# Channel_A.net
KiCad netlist of a schematic drawn in Altium Designer
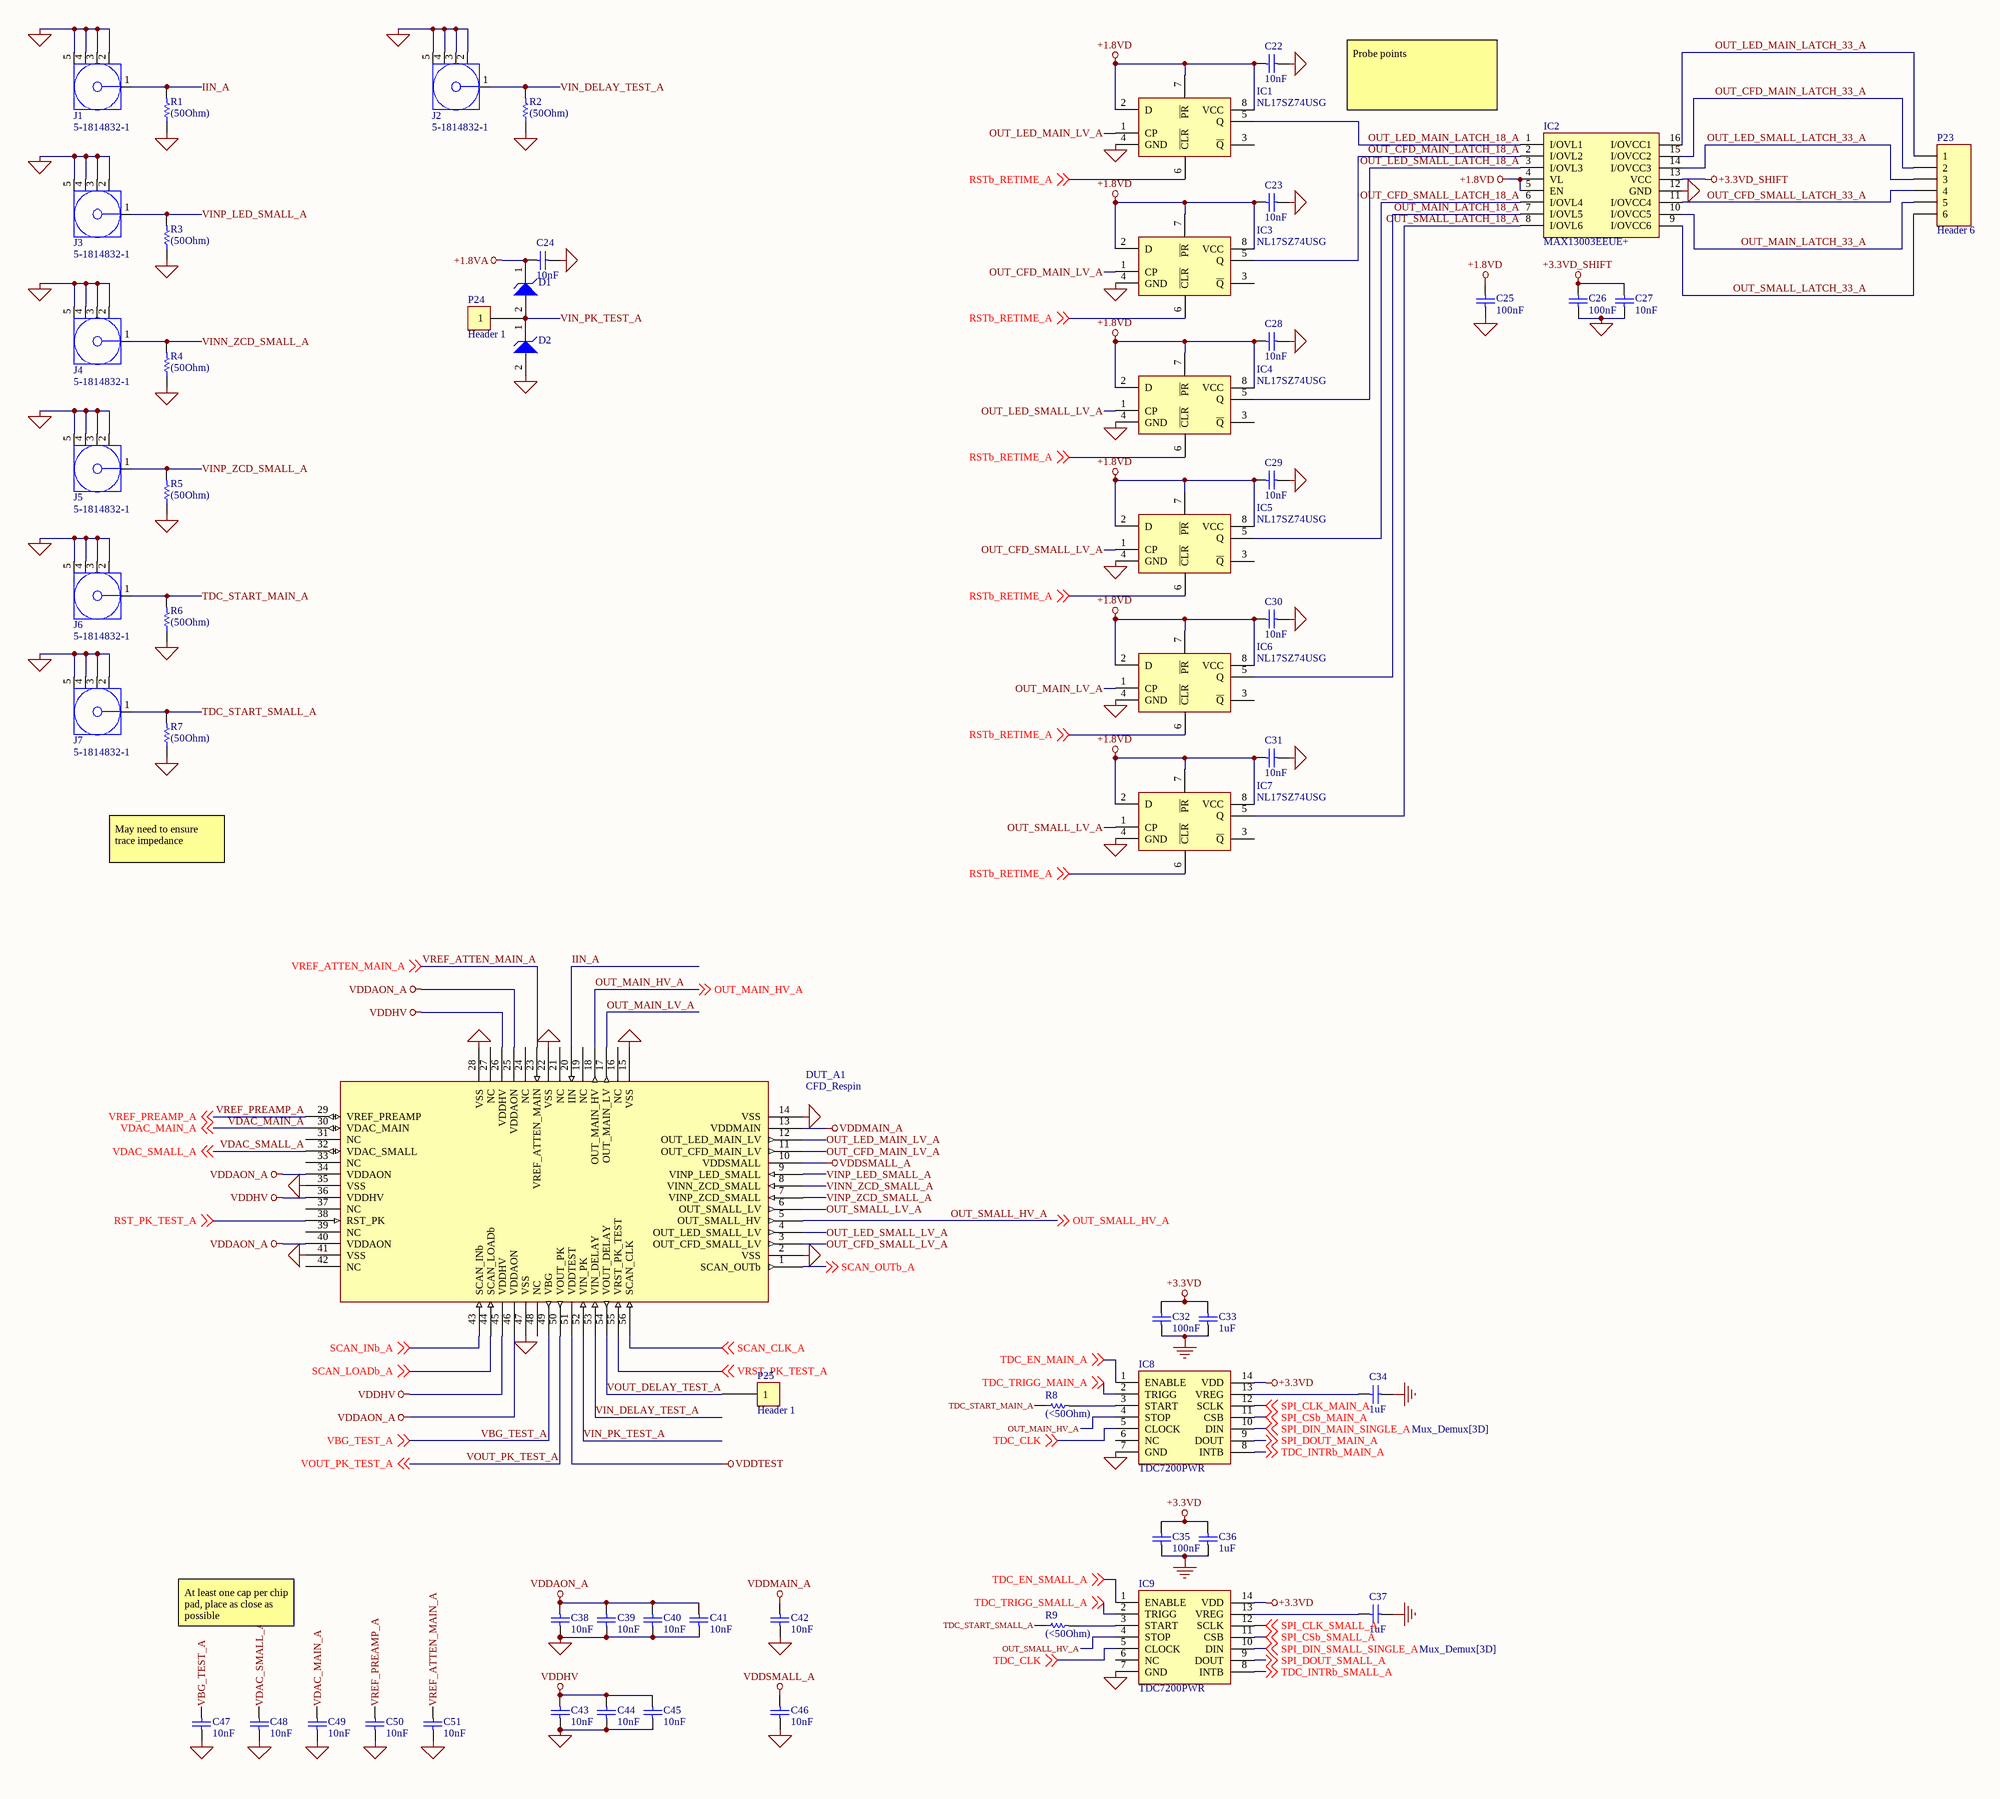
[diagram p0: Channel_A.SchDoc]

(export (version "E")
  (design (tool "Eeschema 10.0.6"))
  (components
    (comp (ref "C22")
      (value "10nF")
      (footprint "CAPC1608X90X35ML10T15")
      (description "0603")
      (fields (field (name "MANUFACTURER") "Murata"))
      (libsource (lib "Altium Content Vault") (part "CAP-NP-2"))
    )
    (comp (ref "C23")
      (value "10nF")
      (footprint "CAPC1608X90X35ML10T15")
      (description "0603")
      (fields (field (name "MANUFACTURER") "Murata"))
      (libsource (lib "Altium Content Vault") (part "CAP-NP-2"))
    )
    (comp (ref "C24")
      (value "10nF")
      (footprint "CAPC1608X90X35ML10T15")
      (description "0603")
      (fields (field (name "MANUFACTURER") "Murata"))
      (libsource (lib "Altium Content Vault") (part "CAP-NP-2"))
    )
    (comp (ref "C25")
      (value "100nF")
      (footprint "CAPC1608X90X35ML10T15")
      (description "0603")
      (fields (field (name "MANUFACTURER") "Murata"))
      (libsource (lib "Altium Content Vault") (part "CAP-NP-2"))
    )
    (comp (ref "C26")
      (value "100nF")
      (footprint "CAPC1608X90X35ML10T15")
      (description "0603")
      (fields (field (name "MANUFACTURER") "Murata"))
      (libsource (lib "Altium Content Vault") (part "CAP-NP-2"))
    )
    (comp (ref "C27")
      (value "10nF")
      (footprint "CAPC1608X90X35ML10T15")
      (description "0603")
      (fields (field (name "MANUFACTURER") "Murata"))
      (libsource (lib "Altium Content Vault") (part "CAP-NP-2"))
    )
    (comp (ref "C28")
      (value "10nF")
      (footprint "CAPC1608X90X35ML10T15")
      (description "0603")
      (fields (field (name "MANUFACTURER") "Murata"))
      (libsource (lib "Altium Content Vault") (part "CAP-NP-2"))
    )
    (comp (ref "C29")
      (value "10nF")
      (footprint "CAPC1608X90X35ML10T15")
      (description "0603")
      (fields (field (name "MANUFACTURER") "Murata"))
      (libsource (lib "Altium Content Vault") (part "CAP-NP-2"))
    )
    (comp (ref "C30")
      (value "10nF")
      (footprint "CAPC1608X90X35ML10T15")
      (description "0603")
      (fields (field (name "MANUFACTURER") "Murata"))
      (libsource (lib "Altium Content Vault") (part "CAP-NP-2"))
    )
    (comp (ref "C31")
      (value "10nF")
      (footprint "CAPC1608X90X35ML10T15")
      (description "0603")
      (fields (field (name "MANUFACTURER") "Murata"))
      (libsource (lib "Altium Content Vault") (part "CAP-NP-2"))
    )
    (comp (ref "C32")
      (value "100nF")
      (footprint "CAPC1608X90X35ML10T15")
      (description "0603")
      (fields (field (name "MANUFACTURER") "Murata"))
      (libsource (lib "Altium Content Vault") (part "CAP-NP-2"))
    )
    (comp (ref "C33")
      (value "1uF")
      (footprint "CAPC1608X90X35ML10T15")
      (description "0603")
      (fields (field (name "MANUFACTURER") "Murata"))
      (libsource (lib "Altium Content Vault") (part "CAP-NP-2"))
    )
    (comp (ref "C34")
      (value "1uF")
      (footprint "CAPC1608X90X35ML10T15")
      (description "0603")
      (fields (field (name "MANUFACTURER") "Murata"))
      (libsource (lib "Altium Content Vault") (part "CAP-NP-2"))
    )
    (comp (ref "C35")
      (value "100nF")
      (footprint "CAPC1608X90X35ML10T15")
      (description "0603")
      (fields (field (name "MANUFACTURER") "Murata"))
      (libsource (lib "Altium Content Vault") (part "CAP-NP-2"))
    )
    (comp (ref "C36")
      (value "1uF")
      (footprint "CAPC1608X90X35ML10T15")
      (description "0603")
      (fields (field (name "MANUFACTURER") "Murata"))
      (libsource (lib "Altium Content Vault") (part "CAP-NP-2"))
    )
    (comp (ref "C37")
      (value "1uF")
      (footprint "CAPC1608X90X35ML10T15")
      (description "0603")
      (fields (field (name "MANUFACTURER") "Murata"))
      (libsource (lib "Altium Content Vault") (part "CAP-NP-2"))
    )
    (comp (ref "C38")
      (value "10nF")
      (footprint "CAPC1608X90X35ML10T15")
      (description "0603")
      (fields (field (name "MANUFACTURER") "Murata"))
      (libsource (lib "Altium Content Vault") (part "CAP-NP-2"))
    )
    (comp (ref "C39")
      (value "10nF")
      (footprint "CAPC1608X90X35ML10T15")
      (description "0603")
      (fields (field (name "MANUFACTURER") "Murata"))
      (libsource (lib "Altium Content Vault") (part "CAP-NP-2"))
    )
    (comp (ref "C40")
      (value "10nF")
      (footprint "CAPC1608X90X35ML10T15")
      (description "0603")
      (fields (field (name "MANUFACTURER") "Murata"))
      (libsource (lib "Altium Content Vault") (part "CAP-NP-2"))
    )
    (comp (ref "C41")
      (value "10nF")
      (footprint "CAPC1608X90X35ML10T15")
      (description "0603")
      (fields (field (name "MANUFACTURER") "Murata"))
      (libsource (lib "Altium Content Vault") (part "CAP-NP-2"))
    )
    (comp (ref "C42")
      (value "10nF")
      (footprint "CAPC1608X90X35ML10T15")
      (description "0603")
      (fields (field (name "MANUFACTURER") "Murata"))
      (libsource (lib "Altium Content Vault") (part "CAP-NP-2"))
    )
    (comp (ref "C43")
      (value "10nF")
      (footprint "CAPC1608X90X35ML10T15")
      (description "0603")
      (fields (field (name "MANUFACTURER") "Murata"))
      (libsource (lib "Altium Content Vault") (part "CAP-NP-2"))
    )
    (comp (ref "C44")
      (value "10nF")
      (footprint "CAPC1608X90X35ML10T15")
      (description "0603")
      (fields (field (name "MANUFACTURER") "Murata"))
      (libsource (lib "Altium Content Vault") (part "CAP-NP-2"))
    )
    (comp (ref "C45")
      (value "10nF")
      (footprint "CAPC1608X90X35ML10T15")
      (description "0603")
      (fields (field (name "MANUFACTURER") "Murata"))
      (libsource (lib "Altium Content Vault") (part "CAP-NP-2"))
    )
    (comp (ref "C46")
      (value "10nF")
      (footprint "CAPC1608X90X35ML10T15")
      (description "0603")
      (fields (field (name "MANUFACTURER") "Murata"))
      (libsource (lib "Altium Content Vault") (part "CAP-NP-2"))
    )
    (comp (ref "C47")
      (value "10nF")
      (footprint "CAPC1608X90X35ML10T15")
      (description "0603")
      (fields (field (name "MANUFACTURER") "Murata"))
      (libsource (lib "Altium Content Vault") (part "CAP-NP-2"))
    )
    (comp (ref "C48")
      (value "10nF")
      (footprint "CAPC1608X90X35ML10T15")
      (description "0603")
      (fields (field (name "MANUFACTURER") "Murata"))
      (libsource (lib "Altium Content Vault") (part "CAP-NP-2"))
    )
    (comp (ref "C49")
      (value "10nF")
      (footprint "CAPC1608X90X35ML10T15")
      (description "0603")
      (fields (field (name "MANUFACTURER") "Murata"))
      (libsource (lib "Altium Content Vault") (part "CAP-NP-2"))
    )
    (comp (ref "C50")
      (value "10nF")
      (footprint "CAPC1608X90X35ML10T15")
      (description "0603")
      (fields (field (name "MANUFACTURER") "Murata"))
      (libsource (lib "Altium Content Vault") (part "CAP-NP-2"))
    )
    (comp (ref "C51")
      (value "10nF")
      (footprint "CAPC1608X90X35ML10T15")
      (description "0603")
      (fields (field (name "MANUFACTURER") "Murata"))
      (libsource (lib "Altium Content Vault") (part "CAP-NP-2"))
    )
    (comp (ref "D1")
      (value "~")
      (footprint "ONSC-SOD-123-2-425-04_V")
      (description "Zener Voltage Regulator, 2-Pin SOD-123, Pb-Free, Tape and Reel")
      (fields (field (name "MANUFACTURER") "On Semiconductor") (field (name "PARTNUMBER") "MMSZ4679T1G"))
      (libsource (lib "Altium Content Vault") (part "ONSC-K1A2-2"))
    )
    (comp (ref "D2")
      (value "~")
      (footprint "ONSC-SOD-123-2-425-04_V")
      (description "Zener Voltage Regulator, 2-Pin SOD-123, Pb-Free, Tape and Reel")
      (fields (field (name "MANUFACTURER") "On Semiconductor") (field (name "PARTNUMBER") "MMSZ4679T1G"))
      (libsource (lib "Altium Content Vault") (part "ONSC-K1A2-2"))
    )
    (comp (ref "DUT_A1")
      (value "CFD_Respin")
      (footprint "QFN50P800X800X80_HS-57N_WIDEVIAS")
      (libsource (lib "intlib") (part "CFD_Respin"))
    )
    (comp (ref "IC1")
      (value "NL17SZ74USG")
      (footprint "SamacSys:SOP50P310X90-8N")
      (description "Flip Flops 1.65-5.5V CMOS Single D-Type")
      (libsource (lib "SamacSys") (part "NL17SZ74USG"))
    )
    (comp (ref "IC2")
      (value "MAX13003EEUE+")
      (footprint "SamacSys:SOP65P640X110-16N")
      (description "Integrated Circuit")
      (libsource (lib "*") (part "MAX13003EEUE+"))
    )
    (comp (ref "IC3")
      (value "NL17SZ74USG")
      (footprint "SamacSys:SOP50P310X90-8N")
      (description "Flip Flops 1.65-5.5V CMOS Single D-Type")
      (libsource (lib "SamacSys") (part "NL17SZ74USG"))
    )
    (comp (ref "IC4")
      (value "NL17SZ74USG")
      (footprint "SamacSys:SOP50P310X90-8N")
      (description "Flip Flops 1.65-5.5V CMOS Single D-Type")
      (libsource (lib "SamacSys") (part "NL17SZ74USG"))
    )
    (comp (ref "IC5")
      (value "NL17SZ74USG")
      (footprint "SamacSys:SOP50P310X90-8N")
      (description "Flip Flops 1.65-5.5V CMOS Single D-Type")
      (libsource (lib "SamacSys") (part "NL17SZ74USG"))
    )
    (comp (ref "IC6")
      (value "NL17SZ74USG")
      (footprint "SamacSys:SOP50P310X90-8N")
      (description "Flip Flops 1.65-5.5V CMOS Single D-Type")
      (libsource (lib "SamacSys") (part "NL17SZ74USG"))
    )
    (comp (ref "IC7")
      (value "NL17SZ74USG")
      (footprint "SamacSys:SOP50P310X90-8N")
      (description "Flip Flops 1.65-5.5V CMOS Single D-Type")
      (libsource (lib "SamacSys") (part "NL17SZ74USG"))
    )
    (comp (ref "IC8")
      (value "TDC7200PWR")
      (footprint "SamacSys:SOP65P640X120-14N")
      (description "Integrated Circuit")
      (libsource (lib "*") (part "TDC7200PWR"))
    )
    (comp (ref "IC9")
      (value "TDC7200PWR")
      (footprint "SamacSys:SOP65P640X120-14N")
      (description "Integrated Circuit")
      (libsource (lib "*") (part "TDC7200PWR"))
    )
    (comp (ref "J1")
      (value "5-1814832-1")
      (footprint "TECO-5-1814832-1_V")
      (fields (field (name "MANUFACTURER") "TE Connectivity"))
      (libsource (lib "Altium Content Vault") (part "CN-S-4F-RF5"))
    )
    (comp (ref "J2")
      (value "5-1814832-1")
      (footprint "TECO-5-1814832-1_V")
      (fields (field (name "MANUFACTURER") "TE Connectivity"))
      (libsource (lib "Altium Content Vault") (part "CN-S-4F-RF5"))
    )
    (comp (ref "J3")
      (value "5-1814832-1")
      (footprint "TECO-5-1814832-1_V")
      (fields (field (name "MANUFACTURER") "TE Connectivity"))
      (libsource (lib "Altium Content Vault") (part "CN-S-4F-RF5"))
    )
    (comp (ref "J4")
      (value "5-1814832-1")
      (footprint "TECO-5-1814832-1_V")
      (fields (field (name "MANUFACTURER") "TE Connectivity"))
      (libsource (lib "Altium Content Vault") (part "CN-S-4F-RF5"))
    )
    (comp (ref "J5")
      (value "5-1814832-1")
      (footprint "TECO-5-1814832-1_V")
      (fields (field (name "MANUFACTURER") "TE Connectivity"))
      (libsource (lib "Altium Content Vault") (part "CN-S-4F-RF5"))
    )
    (comp (ref "J6")
      (value "5-1814832-1")
      (footprint "TECO-5-1814832-1_V")
      (fields (field (name "MANUFACTURER") "TE Connectivity"))
      (libsource (lib "Altium Content Vault") (part "CN-S-4F-RF5"))
    )
    (comp (ref "J7")
      (value "5-1814832-1")
      (footprint "TECO-5-1814832-1_V")
      (fields (field (name "MANUFACTURER") "TE Connectivity"))
      (libsource (lib "Altium Content Vault") (part "CN-S-4F-RF5"))
    )
    (comp (ref "P23")
      (value "Header 6")
      (footprint "HDR1X6")
      (description "Header, 6-Pin")
      (fields (field (name "PUBLISHER") "Altium Limited"))
      (libsource (lib "Miscellaneous Connectors") (part "Header 6"))
    )
    (comp (ref "P24") (value "Header 1") (footprint "Header1") (libsource (lib "intlib") (part "Header 1")))
    (comp (ref "P25") (value "Header 1") (footprint "Header1") (libsource (lib "") (part "Header 1_1")))
    (comp (ref "R1")
      (value "(50Ohm)")
      (footprint "RESC1609X50X30NL8T20")
      (description "0603")
      (fields (field (name "MANUFACTURER") "Vishay Semiconductor"))
      (libsource (lib "Altium Content Vault") (part "RES-2"))
    )
    (comp (ref "R2")
      (value "(50Ohm)")
      (footprint "RESC1609X50X30NL8T20")
      (description "0603")
      (fields (field (name "MANUFACTURER") "Vishay Semiconductor"))
      (libsource (lib "Altium Content Vault") (part "RES-2"))
    )
    (comp (ref "R3")
      (value "(50Ohm)")
      (footprint "RESC1609X50X30NL8T20")
      (description "0603")
      (fields (field (name "MANUFACTURER") "Vishay Semiconductor"))
      (libsource (lib "Altium Content Vault") (part "RES-2"))
    )
    (comp (ref "R4")
      (value "(50Ohm)")
      (footprint "RESC1609X50X30NL8T20")
      (description "0603")
      (fields (field (name "MANUFACTURER") "Vishay Semiconductor"))
      (libsource (lib "Altium Content Vault") (part "RES-2"))
    )
    (comp (ref "R5")
      (value "(50Ohm)")
      (footprint "RESC1609X50X30NL8T20")
      (description "0603")
      (fields (field (name "MANUFACTURER") "Vishay Semiconductor"))
      (libsource (lib "Altium Content Vault") (part "RES-2"))
    )
    (comp (ref "R6")
      (value "(50Ohm)")
      (footprint "RESC1609X50X30NL8T20")
      (description "0603")
      (fields (field (name "MANUFACTURER") "Vishay Semiconductor"))
      (libsource (lib "Altium Content Vault") (part "RES-2"))
    )
    (comp (ref "R7")
      (value "(50Ohm)")
      (footprint "RESC1609X50X30NL8T20")
      (description "0603")
      (fields (field (name "MANUFACTURER") "Vishay Semiconductor"))
      (libsource (lib "Altium Content Vault") (part "RES-2"))
    )
    (comp (ref "R8")
      (value "(<50Ohm)")
      (footprint "RESC1609X50X30NL8T20")
      (description "0603")
      (fields (field (name "MANUFACTURER") "Vishay Semiconductor"))
      (libsource (lib "Altium Content Vault") (part "RES-2"))
    )
    (comp (ref "R9")
      (value "(<50Ohm)")
      (footprint "RESC1609X50X30NL8T20")
      (description "0603")
      (fields (field (name "MANUFACTURER") "Vishay Semiconductor"))
      (libsource (lib "Altium Content Vault") (part "RES-2"))
    )
  )
  (nets
    (net (code "1") (name "+1.8VA") (class "Default")
      (node (ref "C24") (pin "2") (pinfunction "2_2") (pintype "passive"))
      (node (ref "D1") (pin "1") (pinfunction "K_1") (pintype "passive"))
    )
    (net (code "2") (name "+1.8VD") (class "Default")
      (node (ref "C22") (pin "2") (pinfunction "2_2") (pintype "passive"))
      (node (ref "C23") (pin "2") (pinfunction "2_2") (pintype "passive"))
      (node (ref "C25") (pin "2") (pinfunction "2_2") (pintype "passive"))
      (node (ref "C28") (pin "2") (pinfunction "2_2") (pintype "passive"))
      (node (ref "C29") (pin "2") (pinfunction "2_2") (pintype "passive"))
      (node (ref "C30") (pin "2") (pinfunction "2_2") (pintype "passive"))
      (node (ref "C31") (pin "2") (pinfunction "2_2") (pintype "passive"))
      (node (ref "IC1") (pin "2") (pinfunction "D_2") (pintype "passive"))
      (node (ref "IC1") (pin "7") (pinfunction "~{PR}_7") (pintype "passive"))
      (node (ref "IC1") (pin "8") (pinfunction "VCC_8") (pintype "passive"))
      (node (ref "IC2") (pin "4") (pinfunction "VL_4") (pintype "passive"))
      (node (ref "IC2") (pin "5") (pinfunction "EN_5") (pintype "passive"))
      (node (ref "IC3") (pin "2") (pinfunction "D_2") (pintype "passive"))
      (node (ref "IC3") (pin "7") (pinfunction "~{PR}_7") (pintype "passive"))
      (node (ref "IC3") (pin "8") (pinfunction "VCC_8") (pintype "passive"))
      (node (ref "IC4") (pin "2") (pinfunction "D_2") (pintype "passive"))
      (node (ref "IC4") (pin "7") (pinfunction "~{PR}_7") (pintype "passive"))
      (node (ref "IC4") (pin "8") (pinfunction "VCC_8") (pintype "passive"))
      (node (ref "IC5") (pin "2") (pinfunction "D_2") (pintype "passive"))
      (node (ref "IC5") (pin "7") (pinfunction "~{PR}_7") (pintype "passive"))
      (node (ref "IC5") (pin "8") (pinfunction "VCC_8") (pintype "passive"))
      (node (ref "IC6") (pin "2") (pinfunction "D_2") (pintype "passive"))
      (node (ref "IC6") (pin "7") (pinfunction "~{PR}_7") (pintype "passive"))
      (node (ref "IC6") (pin "8") (pinfunction "VCC_8") (pintype "passive"))
      (node (ref "IC7") (pin "2") (pinfunction "D_2") (pintype "passive"))
      (node (ref "IC7") (pin "7") (pinfunction "~{PR}_7") (pintype "passive"))
      (node (ref "IC7") (pin "8") (pinfunction "VCC_8") (pintype "passive"))
    )
    (net (code "3") (name "+3.3VD") (class "Default")
      (node (ref "C32") (pin "1") (pinfunction "1_1") (pintype "passive"))
      (node (ref "C33") (pin "1") (pinfunction "1_1") (pintype "passive"))
      (node (ref "C35") (pin "1") (pinfunction "1_1") (pintype "passive"))
      (node (ref "C36") (pin "1") (pinfunction "1_1") (pintype "passive"))
      (node (ref "IC8") (pin "14") (pinfunction "VDD_14") (pintype "passive"))
      (node (ref "IC9") (pin "14") (pinfunction "VDD_14") (pintype "passive"))
    )
    (net (code "4") (name "+3.3VD_SHIFT") (class "Default")
      (node (ref "C26") (pin "2") (pinfunction "2_2") (pintype "passive"))
      (node (ref "C27") (pin "2") (pinfunction "2_2") (pintype "passive"))
      (node (ref "IC2") (pin "13") (pinfunction "VCC_13") (pintype "passive"))
    )
    (net (code "5") (name "/IIN_A") (class "Default")
      (node (ref "DUT_A1") (pin "20") (pinfunction "IIN_20") (pintype "input"))
      (node (ref "J1") (pin "1") (pinfunction "1_1") (pintype "passive"))
      (node (ref "R1") (pin "2") (pinfunction "2_2") (pintype "passive"))
    )
    (net (code "6") (name "/OUT_CFD_MAIN_LATCH_18_A") (class "Default")
      (node (ref "IC2") (pin "2") (pinfunction "I/OVL2_2") (pintype "passive"))
      (node (ref "IC3") (pin "5") (pinfunction "Q_5") (pintype "passive"))
    )
    (net (code "7") (name "/OUT_CFD_MAIN_LATCH_33_A") (class "Default")
      (node (ref "IC2") (pin "15") (pinfunction "I/OVCC2_15") (pintype "passive"))
      (node (ref "P23") (pin "2") (pinfunction "2_2") (pintype "passive"))
    )
    (net (code "8") (name "/OUT_CFD_MAIN_LV_A") (class "Default")
      (node (ref "DUT_A1") (pin "11") (pinfunction "OUT_CFD_MAIN_LV_11") (pintype "output"))
      (node (ref "IC3") (pin "1") (pinfunction "CP_1") (pintype "passive"))
    )
    (net (code "9") (name "/OUT_CFD_SMALL_LATCH_18_A") (class "Default")
      (node (ref "IC2") (pin "6") (pinfunction "I/OVL4_6") (pintype "passive"))
      (node (ref "IC5") (pin "5") (pinfunction "Q_5") (pintype "passive"))
    )
    (net (code "10") (name "/OUT_CFD_SMALL_LATCH_33_A") (class "Default")
      (node (ref "IC2") (pin "11") (pinfunction "I/OVCC4_11") (pintype "passive"))
      (node (ref "P23") (pin "4") (pinfunction "4_4") (pintype "passive"))
    )
    (net (code "11") (name "/OUT_CFD_SMALL_LV_A") (class "Default")
      (node (ref "DUT_A1") (pin "3") (pinfunction "OUT_CFD_SMALL_LV_3") (pintype "output"))
      (node (ref "IC5") (pin "1") (pinfunction "CP_1") (pintype "passive"))
    )
    (net (code "12") (name "/OUT_LED_MAIN_LATCH_18_A") (class "Default")
      (node (ref "IC1") (pin "5") (pinfunction "Q_5") (pintype "passive"))
      (node (ref "IC2") (pin "1") (pinfunction "I/OVL1_1") (pintype "passive"))
    )
    (net (code "13") (name "/OUT_LED_MAIN_LATCH_33_A") (class "Default")
      (node (ref "IC2") (pin "16") (pinfunction "I/OVCC1_16") (pintype "passive"))
      (node (ref "P23") (pin "1") (pinfunction "1_1") (pintype "passive"))
    )
    (net (code "14") (name "/OUT_LED_MAIN_LV_A") (class "Default")
      (node (ref "DUT_A1") (pin "12") (pinfunction "OUT_LED_MAIN_LV_12") (pintype "output"))
      (node (ref "IC1") (pin "1") (pinfunction "CP_1") (pintype "passive"))
    )
    (net (code "15") (name "/OUT_LED_SMALL_LATCH_18_A") (class "Default")
      (node (ref "IC2") (pin "3") (pinfunction "I/OVL3_3") (pintype "passive"))
      (node (ref "IC4") (pin "5") (pinfunction "Q_5") (pintype "passive"))
    )
    (net (code "16") (name "/OUT_LED_SMALL_LATCH_33_A") (class "Default")
      (node (ref "IC2") (pin "14") (pinfunction "I/OVCC3_14") (pintype "passive"))
      (node (ref "P23") (pin "3") (pinfunction "3_3") (pintype "passive"))
    )
    (net (code "17") (name "/OUT_LED_SMALL_LV_A") (class "Default")
      (node (ref "DUT_A1") (pin "4") (pinfunction "OUT_LED_SMALL_LV_4") (pintype "output"))
      (node (ref "IC4") (pin "1") (pinfunction "CP_1") (pintype "passive"))
    )
    (net (code "18") (name "/OUT_MAIN_LATCH_18_A") (class "Default")
      (node (ref "IC2") (pin "7") (pinfunction "I/OVL5_7") (pintype "passive"))
      (node (ref "IC6") (pin "5") (pinfunction "Q_5") (pintype "passive"))
    )
    (net (code "19") (name "/OUT_MAIN_LATCH_33_A") (class "Default")
      (node (ref "IC2") (pin "10") (pinfunction "I/OVCC5_10") (pintype "passive"))
      (node (ref "P23") (pin "5") (pinfunction "5_5") (pintype "passive"))
    )
    (net (code "20") (name "/OUT_MAIN_LV_A") (class "Default")
      (node (ref "DUT_A1") (pin "17") (pinfunction "OUT_MAIN_LV_17") (pintype "output"))
      (node (ref "IC6") (pin "1") (pinfunction "CP_1") (pintype "passive"))
    )
    (net (code "21") (name "/OUT_SMALL_LATCH_18_A") (class "Default")
      (node (ref "IC2") (pin "8") (pinfunction "I/OVL6_8") (pintype "passive"))
      (node (ref "IC7") (pin "5") (pinfunction "Q_5") (pintype "passive"))
    )
    (net (code "22") (name "/OUT_SMALL_LATCH_33_A") (class "Default")
      (node (ref "IC2") (pin "9") (pinfunction "I/OVCC6_9") (pintype "passive"))
      (node (ref "P23") (pin "6") (pinfunction "6_6") (pintype "passive"))
    )
    (net (code "23") (name "/OUT_SMALL_LV_A") (class "Default")
      (node (ref "DUT_A1") (pin "6") (pinfunction "OUT_SMALL_LV_6") (pintype "output"))
      (node (ref "IC7") (pin "1") (pinfunction "CP_1") (pintype "passive"))
    )
    (net (code "24") (name "/TDC_START_MAIN_A") (class "Default")
      (node (ref "J6") (pin "1") (pinfunction "1_1") (pintype "passive"))
      (node (ref "R6") (pin "2") (pinfunction "2_2") (pintype "passive"))
      (node (ref "R8") (pin "1") (pinfunction "1_1") (pintype "passive"))
    )
    (net (code "25") (name "/TDC_START_SMALL_A") (class "Default")
      (node (ref "J7") (pin "1") (pinfunction "1_1") (pintype "passive"))
      (node (ref "R7") (pin "2") (pinfunction "2_2") (pintype "passive"))
      (node (ref "R9") (pin "1") (pinfunction "1_1") (pintype "passive"))
    )
    (net (code "26") (name "/VINN_ZCD_SMALL_A") (class "Default")
      (node (ref "DUT_A1") (pin "8") (pinfunction "VINN_ZCD_SMALL_8") (pintype "input"))
      (node (ref "J4") (pin "1") (pinfunction "1_1") (pintype "passive"))
      (node (ref "R4") (pin "2") (pinfunction "2_2") (pintype "passive"))
    )
    (net (code "27") (name "/VINP_LED_SMALL_A") (class "Default")
      (node (ref "DUT_A1") (pin "9") (pinfunction "VINP_LED_SMALL_9") (pintype "input"))
      (node (ref "J3") (pin "1") (pinfunction "1_1") (pintype "passive"))
      (node (ref "R3") (pin "2") (pinfunction "2_2") (pintype "passive"))
    )
    (net (code "28") (name "/VINP_ZCD_SMALL_A") (class "Default")
      (node (ref "DUT_A1") (pin "7") (pinfunction "VINP_ZCD_SMALL_7") (pintype "input"))
      (node (ref "J5") (pin "1") (pinfunction "1_1") (pintype "passive"))
      (node (ref "R5") (pin "2") (pinfunction "2_2") (pintype "passive"))
    )
    (net (code "29") (name "/VIN_DELAY_TEST_A") (class "Default")
      (node (ref "DUT_A1") (pin "53") (pinfunction "VIN_DELAY_53") (pintype "input"))
      (node (ref "J2") (pin "1") (pinfunction "1_1") (pintype "passive"))
      (node (ref "R2") (pin "2") (pinfunction "2_2") (pintype "passive"))
    )
    (net (code "30") (name "/VIN_PK_TEST_A") (class "Default")
      (node (ref "D1") (pin "2") (pinfunction "A_2") (pintype "passive"))
      (node (ref "D2") (pin "1") (pinfunction "K_1") (pintype "passive"))
      (node (ref "DUT_A1") (pin "52") (pinfunction "VIN_PK_52") (pintype "input"))
      (node (ref "P24") (pin "1") (pinfunction "1_1") (pintype "passive"))
    )
    (net (code "31") (name "/VOUT_DELAY_TEST_A") (class "Default")
      (node (ref "DUT_A1") (pin "54") (pinfunction "VOUT_DELAY_54") (pintype "output"))
      (node (ref "P25") (pin "1") (pinfunction "1_1") (pintype "passive"))
    )
    (net (code "32") (name "GND") (class "Default")
      (node (ref "C22") (pin "1") (pinfunction "1_1") (pintype "passive"))
      (node (ref "C23") (pin "1") (pinfunction "1_1") (pintype "passive"))
      (node (ref "C24") (pin "1") (pinfunction "1_1") (pintype "passive"))
      (node (ref "C25") (pin "1") (pinfunction "1_1") (pintype "passive"))
      (node (ref "C26") (pin "1") (pinfunction "1_1") (pintype "passive"))
      (node (ref "C27") (pin "1") (pinfunction "1_1") (pintype "passive"))
      (node (ref "C28") (pin "1") (pinfunction "1_1") (pintype "passive"))
      (node (ref "C29") (pin "1") (pinfunction "1_1") (pintype "passive"))
      (node (ref "C30") (pin "1") (pinfunction "1_1") (pintype "passive"))
      (node (ref "C31") (pin "1") (pinfunction "1_1") (pintype "passive"))
      (node (ref "C32") (pin "2") (pinfunction "2_2") (pintype "passive"))
      (node (ref "C33") (pin "2") (pinfunction "2_2") (pintype "passive"))
      (node (ref "C34") (pin "2") (pinfunction "2_2") (pintype "passive"))
      (node (ref "C35") (pin "2") (pinfunction "2_2") (pintype "passive"))
      (node (ref "C36") (pin "2") (pinfunction "2_2") (pintype "passive"))
      (node (ref "C37") (pin "2") (pinfunction "2_2") (pintype "passive"))
      (node (ref "C38") (pin "1") (pinfunction "1_1") (pintype "passive"))
      (node (ref "C39") (pin "1") (pinfunction "1_1") (pintype "passive"))
      (node (ref "C40") (pin "1") (pinfunction "1_1") (pintype "passive"))
      (node (ref "C41") (pin "1") (pinfunction "1_1") (pintype "passive"))
      (node (ref "C42") (pin "1") (pinfunction "1_1") (pintype "passive"))
      (node (ref "C43") (pin "1") (pinfunction "1_1") (pintype "passive"))
      (node (ref "C44") (pin "1") (pinfunction "1_1") (pintype "passive"))
      (node (ref "C45") (pin "1") (pinfunction "1_1") (pintype "passive"))
      (node (ref "C46") (pin "1") (pinfunction "1_1") (pintype "passive"))
      (node (ref "C47") (pin "1") (pinfunction "1_1") (pintype "passive"))
      (node (ref "C48") (pin "1") (pinfunction "1_1") (pintype "passive"))
      (node (ref "C49") (pin "1") (pinfunction "1_1") (pintype "passive"))
      (node (ref "C50") (pin "1") (pinfunction "1_1") (pintype "passive"))
      (node (ref "C51") (pin "1") (pinfunction "1_1") (pintype "passive"))
      (node (ref "D2") (pin "2") (pinfunction "A_2") (pintype "passive"))
      (node (ref "DUT_A1") (pin "14") (pinfunction "VSS_14") (pintype "power_in"))
      (node (ref "DUT_A1") (pin "15") (pinfunction "VSS_15") (pintype "power_in"))
      (node (ref "DUT_A1") (pin "2") (pinfunction "VSS_2") (pintype "power_in"))
      (node (ref "DUT_A1") (pin "22") (pinfunction "VSS_22") (pintype "power_in"))
      (node (ref "DUT_A1") (pin "28") (pinfunction "VSS_28") (pintype "power_in"))
      (node (ref "DUT_A1") (pin "35") (pinfunction "VSS_35") (pintype "power_in"))
      (node (ref "DUT_A1") (pin "41") (pinfunction "VSS_41") (pintype "power_in"))
      (node (ref "DUT_A1") (pin "47") (pinfunction "VSS_47") (pintype "power_in"))
      (node (ref "IC1") (pin "4") (pinfunction "GND_4") (pintype "passive"))
      (node (ref "IC2") (pin "12") (pinfunction "GND_12") (pintype "passive"))
      (node (ref "IC3") (pin "4") (pinfunction "GND_4") (pintype "passive"))
      (node (ref "IC4") (pin "4") (pinfunction "GND_4") (pintype "passive"))
      (node (ref "IC5") (pin "4") (pinfunction "GND_4") (pintype "passive"))
      (node (ref "IC6") (pin "4") (pinfunction "GND_4") (pintype "passive"))
      (node (ref "IC7") (pin "4") (pinfunction "GND_4") (pintype "passive"))
      (node (ref "IC8") (pin "7") (pinfunction "GND_7") (pintype "passive"))
      (node (ref "IC9") (pin "7") (pinfunction "GND_7") (pintype "passive"))
      (node (ref "J1") (pin "2") (pinfunction "2_2") (pintype "passive"))
      (node (ref "J1") (pin "3") (pinfunction "3_3") (pintype "passive"))
      (node (ref "J1") (pin "4") (pinfunction "4_4") (pintype "passive"))
      (node (ref "J1") (pin "5") (pinfunction "5_5") (pintype "passive"))
      (node (ref "J2") (pin "2") (pinfunction "2_2") (pintype "passive"))
      (node (ref "J2") (pin "3") (pinfunction "3_3") (pintype "passive"))
      (node (ref "J2") (pin "4") (pinfunction "4_4") (pintype "passive"))
      (node (ref "J2") (pin "5") (pinfunction "5_5") (pintype "passive"))
      (node (ref "J3") (pin "2") (pinfunction "2_2") (pintype "passive"))
      (node (ref "J3") (pin "3") (pinfunction "3_3") (pintype "passive"))
      (node (ref "J3") (pin "4") (pinfunction "4_4") (pintype "passive"))
      (node (ref "J3") (pin "5") (pinfunction "5_5") (pintype "passive"))
      (node (ref "J4") (pin "2") (pinfunction "2_2") (pintype "passive"))
      (node (ref "J4") (pin "3") (pinfunction "3_3") (pintype "passive"))
      (node (ref "J4") (pin "4") (pinfunction "4_4") (pintype "passive"))
      (node (ref "J4") (pin "5") (pinfunction "5_5") (pintype "passive"))
      (node (ref "J5") (pin "2") (pinfunction "2_2") (pintype "passive"))
      (node (ref "J5") (pin "3") (pinfunction "3_3") (pintype "passive"))
      (node (ref "J5") (pin "4") (pinfunction "4_4") (pintype "passive"))
      (node (ref "J5") (pin "5") (pinfunction "5_5") (pintype "passive"))
      (node (ref "J6") (pin "2") (pinfunction "2_2") (pintype "passive"))
      (node (ref "J6") (pin "3") (pinfunction "3_3") (pintype "passive"))
      (node (ref "J6") (pin "4") (pinfunction "4_4") (pintype "passive"))
      (node (ref "J6") (pin "5") (pinfunction "5_5") (pintype "passive"))
      (node (ref "J7") (pin "2") (pinfunction "2_2") (pintype "passive"))
      (node (ref "J7") (pin "3") (pinfunction "3_3") (pintype "passive"))
      (node (ref "J7") (pin "4") (pinfunction "4_4") (pintype "passive"))
      (node (ref "J7") (pin "5") (pinfunction "5_5") (pintype "passive"))
      (node (ref "R1") (pin "1") (pinfunction "1_1") (pintype "passive"))
      (node (ref "R2") (pin "1") (pinfunction "1_1") (pintype "passive"))
      (node (ref "R3") (pin "1") (pinfunction "1_1") (pintype "passive"))
      (node (ref "R4") (pin "1") (pinfunction "1_1") (pintype "passive"))
      (node (ref "R5") (pin "1") (pinfunction "1_1") (pintype "passive"))
      (node (ref "R6") (pin "1") (pinfunction "1_1") (pintype "passive"))
      (node (ref "R7") (pin "1") (pinfunction "1_1") (pintype "passive"))
    )
    (net (code "33") (name "Net-(IC8-START)") (class "Default")
      (node (ref "IC8") (pin "3") (pinfunction "START_3") (pintype "passive"))
      (node (ref "R8") (pin "2") (pinfunction "2_2") (pintype "passive"))
    )
    (net (code "34") (name "Net-(IC8-VREG)") (class "Default")
      (node (ref "C34") (pin "1") (pinfunction "1_1") (pintype "passive"))
      (node (ref "IC8") (pin "13") (pinfunction "VREG_13") (pintype "passive"))
    )
    (net (code "35") (name "Net-(IC9-START)") (class "Default")
      (node (ref "IC9") (pin "3") (pinfunction "START_3") (pintype "passive"))
      (node (ref "R9") (pin "2") (pinfunction "2_2") (pintype "passive"))
    )
    (net (code "36") (name "Net-(IC9-VREG)") (class "Default")
      (node (ref "C37") (pin "1") (pinfunction "1_1") (pintype "passive"))
      (node (ref "IC9") (pin "13") (pinfunction "VREG_13") (pintype "passive"))
    )
    (net (code "37") (name "OUT_MAIN_HV_A") (class "Default")
      (node (ref "DUT_A1") (pin "18") (pinfunction "OUT_MAIN_HV_18") (pintype "output"))
      (node (ref "IC8") (pin "4") (pinfunction "STOP_4") (pintype "passive"))
    )
    (net (code "38") (name "OUT_SMALL_HV_A") (class "Default")
      (node (ref "DUT_A1") (pin "5") (pinfunction "OUT_SMALL_HV_5") (pintype "output"))
      (node (ref "IC9") (pin "4") (pinfunction "STOP_4") (pintype "passive"))
    )
    (net (code "39") (name "RST_PK_TEST_A") (class "Default")
      (node (ref "DUT_A1") (pin "38") (pinfunction "RST_PK_38") (pintype "input"))
    )
    (net (code "40") (name "RSTb_RETIME_A") (class "Default")
      (node (ref "IC1") (pin "6") (pinfunction "~{CLR}_6") (pintype "passive"))
      (node (ref "IC3") (pin "6") (pinfunction "~{CLR}_6") (pintype "passive"))
      (node (ref "IC4") (pin "6") (pinfunction "~{CLR}_6") (pintype "passive"))
      (node (ref "IC5") (pin "6") (pinfunction "~{CLR}_6") (pintype "passive"))
      (node (ref "IC6") (pin "6") (pinfunction "~{CLR}_6") (pintype "passive"))
      (node (ref "IC7") (pin "6") (pinfunction "~{CLR}_6") (pintype "passive"))
    )
    (net (code "41") (name "SCAN_CLK_A") (class "Default")
      (node (ref "DUT_A1") (pin "56") (pinfunction "SCAN_CLK_56") (pintype "input"))
    )
    (net (code "42") (name "SCAN_INb_A") (class "Default")
      (node (ref "DUT_A1") (pin "43") (pinfunction "SCAN_INb_43") (pintype "input"))
    )
    (net (code "43") (name "SCAN_LOADb_A") (class "Default")
      (node (ref "DUT_A1") (pin "44") (pinfunction "SCAN_LOADb_44") (pintype "input"))
    )
    (net (code "44") (name "SCAN_OUTb_A") (class "Default")
      (node (ref "DUT_A1") (pin "1") (pinfunction "SCAN_OUTb_1") (pintype "output"))
    )
    (net (code "45") (name "SPI_CLK_MAIN_A") (class "Default")
      (node (ref "IC8") (pin "12") (pinfunction "SCLK_12") (pintype "passive"))
    )
    (net (code "46") (name "SPI_CLK_SMALL_A") (class "Default")
      (node (ref "IC9") (pin "12") (pinfunction "SCLK_12") (pintype "passive"))
    )
    (net (code "47") (name "SPI_CSb_MAIN_A") (class "Default")
      (node (ref "IC8") (pin "11") (pinfunction "CSB_11") (pintype "passive"))
    )
    (net (code "48") (name "SPI_CSb_SMALL_A") (class "Default")
      (node (ref "IC9") (pin "11") (pinfunction "CSB_11") (pintype "passive"))
    )
    (net (code "49") (name "SPI_DIN_MAIN_SINGLE_A") (class "Default")
      (node (ref "IC8") (pin "10") (pinfunction "DIN_10") (pintype "passive"))
    )
    (net (code "50") (name "SPI_DIN_SMALL_SINGLE_A") (class "Default")
      (node (ref "IC9") (pin "10") (pinfunction "DIN_10") (pintype "passive"))
    )
    (net (code "51") (name "SPI_DOUT_MAIN_A") (class "Default")
      (node (ref "IC8") (pin "9") (pinfunction "DOUT_9") (pintype "passive"))
    )
    (net (code "52") (name "SPI_DOUT_SMALL_A") (class "Default")
      (node (ref "IC9") (pin "9") (pinfunction "DOUT_9") (pintype "passive"))
    )
    (net (code "53") (name "TDC_CLK") (class "Default")
      (node (ref "IC8") (pin "5") (pinfunction "CLOCK_5") (pintype "passive"))
      (node (ref "IC9") (pin "5") (pinfunction "CLOCK_5") (pintype "passive"))
    )
    (net (code "54") (name "TDC_EN_MAIN_A") (class "Default")
      (node (ref "IC8") (pin "1") (pinfunction "ENABLE_1") (pintype "passive"))
    )
    (net (code "55") (name "TDC_EN_SMALL_A") (class "Default")
      (node (ref "IC9") (pin "1") (pinfunction "ENABLE_1") (pintype "passive"))
    )
    (net (code "56") (name "TDC_INTRb_MAIN_A") (class "Default")
      (node (ref "IC8") (pin "8") (pinfunction "INTB_8") (pintype "passive"))
    )
    (net (code "57") (name "TDC_INTRb_SMALL_A") (class "Default")
      (node (ref "IC9") (pin "8") (pinfunction "INTB_8") (pintype "passive"))
    )
    (net (code "58") (name "TDC_TRIGG_MAIN_A") (class "Default")
      (node (ref "IC8") (pin "2") (pinfunction "TRIGG_2") (pintype "passive"))
    )
    (net (code "59") (name "TDC_TRIGG_SMALL_A") (class "Default")
      (node (ref "IC9") (pin "2") (pinfunction "TRIGG_2") (pintype "passive"))
    )
    (net (code "60") (name "VBG_TEST_A") (class "Default")
      (node (ref "C47") (pin "2") (pinfunction "2_2") (pintype "passive"))
      (node (ref "DUT_A1") (pin "49") (pinfunction "VBG_49") (pintype "output"))
    )
    (net (code "61") (name "VDAC_MAIN_A") (class "Default")
      (node (ref "C49") (pin "2") (pinfunction "2_2") (pintype "passive"))
      (node (ref "DUT_A1") (pin "30") (pinfunction "VDAC_MAIN_30") (pintype "bidirectional"))
    )
    (net (code "62") (name "VDAC_SMALL_A") (class "Default")
      (node (ref "C48") (pin "2") (pinfunction "2_2") (pintype "passive"))
      (node (ref "DUT_A1") (pin "32") (pinfunction "VDAC_SMALL_32") (pintype "bidirectional"))
    )
    (net (code "63") (name "VDDAON_A") (class "Default")
      (node (ref "C38") (pin "2") (pinfunction "2_2") (pintype "passive"))
      (node (ref "C39") (pin "2") (pinfunction "2_2") (pintype "passive"))
      (node (ref "C40") (pin "2") (pinfunction "2_2") (pintype "passive"))
      (node (ref "C41") (pin "2") (pinfunction "2_2") (pintype "passive"))
      (node (ref "DUT_A1") (pin "25") (pinfunction "VDDAON_25") (pintype "power_in"))
      (node (ref "DUT_A1") (pin "34") (pinfunction "VDDAON_34") (pintype "power_in"))
      (node (ref "DUT_A1") (pin "40") (pinfunction "VDDAON_40") (pintype "power_in"))
      (node (ref "DUT_A1") (pin "46") (pinfunction "VDDAON_46") (pintype "power_in"))
    )
    (net (code "64") (name "VDDHV") (class "Default")
      (node (ref "C43") (pin "2") (pinfunction "2_2") (pintype "passive"))
      (node (ref "C44") (pin "2") (pinfunction "2_2") (pintype "passive"))
      (node (ref "C45") (pin "2") (pinfunction "2_2") (pintype "passive"))
      (node (ref "DUT_A1") (pin "26") (pinfunction "VDDHV_26") (pintype "power_in"))
      (node (ref "DUT_A1") (pin "36") (pinfunction "VDDHV_36") (pintype "power_in"))
      (node (ref "DUT_A1") (pin "45") (pinfunction "VDDHV_45") (pintype "power_in"))
    )
    (net (code "65") (name "VDDMAIN_A") (class "Default")
      (node (ref "C42") (pin "2") (pinfunction "2_2") (pintype "passive"))
      (node (ref "DUT_A1") (pin "13") (pinfunction "VDDMAIN_13") (pintype "power_in"))
    )
    (net (code "66") (name "VDDSMALL_A") (class "Default")
      (node (ref "C46") (pin "2") (pinfunction "2_2") (pintype "passive"))
      (node (ref "DUT_A1") (pin "10") (pinfunction "VDDSMALL_10") (pintype "power_in"))
    )
    (net (code "67") (name "VDDTEST") (class "Default")
      (node (ref "DUT_A1") (pin "51") (pinfunction "VDDTEST_51") (pintype "power_in"))
    )
    (net (code "68") (name "VOUT_PK_TEST_A") (class "Default")
      (node (ref "DUT_A1") (pin "50") (pinfunction "VOUT_PK_50") (pintype "output"))
    )
    (net (code "69") (name "VREF_ATTEN_MAIN_A") (class "Default")
      (node (ref "C51") (pin "2") (pinfunction "2_2") (pintype "passive"))
      (node (ref "DUT_A1") (pin "23") (pinfunction "VREF_ATTEN_MAIN_23") (pintype "input"))
    )
    (net (code "70") (name "VREF_PREAMP_A") (class "Default")
      (node (ref "C50") (pin "2") (pinfunction "2_2") (pintype "passive"))
      (node (ref "DUT_A1") (pin "29") (pinfunction "VREF_PREAMP_29") (pintype "bidirectional"))
    )
    (net (code "71") (name "VRST_PK_TEST_A") (class "Default")
      (node (ref "DUT_A1") (pin "55") (pinfunction "VRST_PK_TEST_55") (pintype "input"))
    )
    (net (code "72") (name "unconnected-(DUT_A1-NC-Pad16)") (class "Default")
      (node (ref "DUT_A1") (pin "16") (pinfunction "NC_16") (pintype "passive"))
    )
    (net (code "73") (name "unconnected-(DUT_A1-NC-Pad19)") (class "Default")
      (node (ref "DUT_A1") (pin "19") (pinfunction "NC_19") (pintype "passive"))
    )
    (net (code "74") (name "unconnected-(DUT_A1-NC-Pad21)") (class "Default")
      (node (ref "DUT_A1") (pin "21") (pinfunction "NC_21") (pintype "passive"))
    )
    (net (code "75") (name "unconnected-(DUT_A1-NC-Pad24)") (class "Default")
      (node (ref "DUT_A1") (pin "24") (pinfunction "NC_24") (pintype "passive"))
    )
    (net (code "76") (name "unconnected-(DUT_A1-NC-Pad27)") (class "Default")
      (node (ref "DUT_A1") (pin "27") (pinfunction "NC_27") (pintype "passive"))
    )
    (net (code "77") (name "unconnected-(DUT_A1-NC-Pad31)") (class "Default")
      (node (ref "DUT_A1") (pin "31") (pinfunction "NC_31") (pintype "passive"))
    )
    (net (code "78") (name "unconnected-(DUT_A1-NC-Pad33)") (class "Default")
      (node (ref "DUT_A1") (pin "33") (pinfunction "NC_33") (pintype "passive"))
    )
    (net (code "79") (name "unconnected-(DUT_A1-NC-Pad37)") (class "Default")
      (node (ref "DUT_A1") (pin "37") (pinfunction "NC_37") (pintype "passive"))
    )
    (net (code "80") (name "unconnected-(DUT_A1-NC-Pad39)") (class "Default")
      (node (ref "DUT_A1") (pin "39") (pinfunction "NC_39") (pintype "passive"))
    )
    (net (code "81") (name "unconnected-(DUT_A1-NC-Pad42)") (class "Default")
      (node (ref "DUT_A1") (pin "42") (pinfunction "NC_42") (pintype "passive"))
    )
    (net (code "82") (name "unconnected-(DUT_A1-NC-Pad48)") (class "Default")
      (node (ref "DUT_A1") (pin "48") (pinfunction "NC_48") (pintype "passive"))
    )
    (net (code "83") (name "unconnected-(IC1-~{Q}-Pad3)") (class "Default")
      (node (ref "IC1") (pin "3") (pinfunction "~{Q}_3") (pintype "passive"))
    )
    (net (code "84") (name "unconnected-(IC3-~{Q}-Pad3)") (class "Default")
      (node (ref "IC3") (pin "3") (pinfunction "~{Q}_3") (pintype "passive"))
    )
    (net (code "85") (name "unconnected-(IC4-~{Q}-Pad3)") (class "Default")
      (node (ref "IC4") (pin "3") (pinfunction "~{Q}_3") (pintype "passive"))
    )
    (net (code "86") (name "unconnected-(IC5-~{Q}-Pad3)") (class "Default")
      (node (ref "IC5") (pin "3") (pinfunction "~{Q}_3") (pintype "passive"))
    )
    (net (code "87") (name "unconnected-(IC6-~{Q}-Pad3)") (class "Default")
      (node (ref "IC6") (pin "3") (pinfunction "~{Q}_3") (pintype "passive"))
    )
    (net (code "88") (name "unconnected-(IC7-~{Q}-Pad3)") (class "Default")
      (node (ref "IC7") (pin "3") (pinfunction "~{Q}_3") (pintype "passive"))
    )
    (net (code "89") (name "unconnected-(IC8-NC-Pad6)") (class "Default")
      (node (ref "IC8") (pin "6") (pinfunction "NC_6") (pintype "passive"))
    )
    (net (code "90") (name "unconnected-(IC9-NC-Pad6)") (class "Default")
      (node (ref "IC9") (pin "6") (pinfunction "NC_6") (pintype "passive"))
    )
  )
)
